# SparkFun_LoRaSerial_868MHz_-_1W.net
KiCad netlist of a schematic drawn in EAGLE
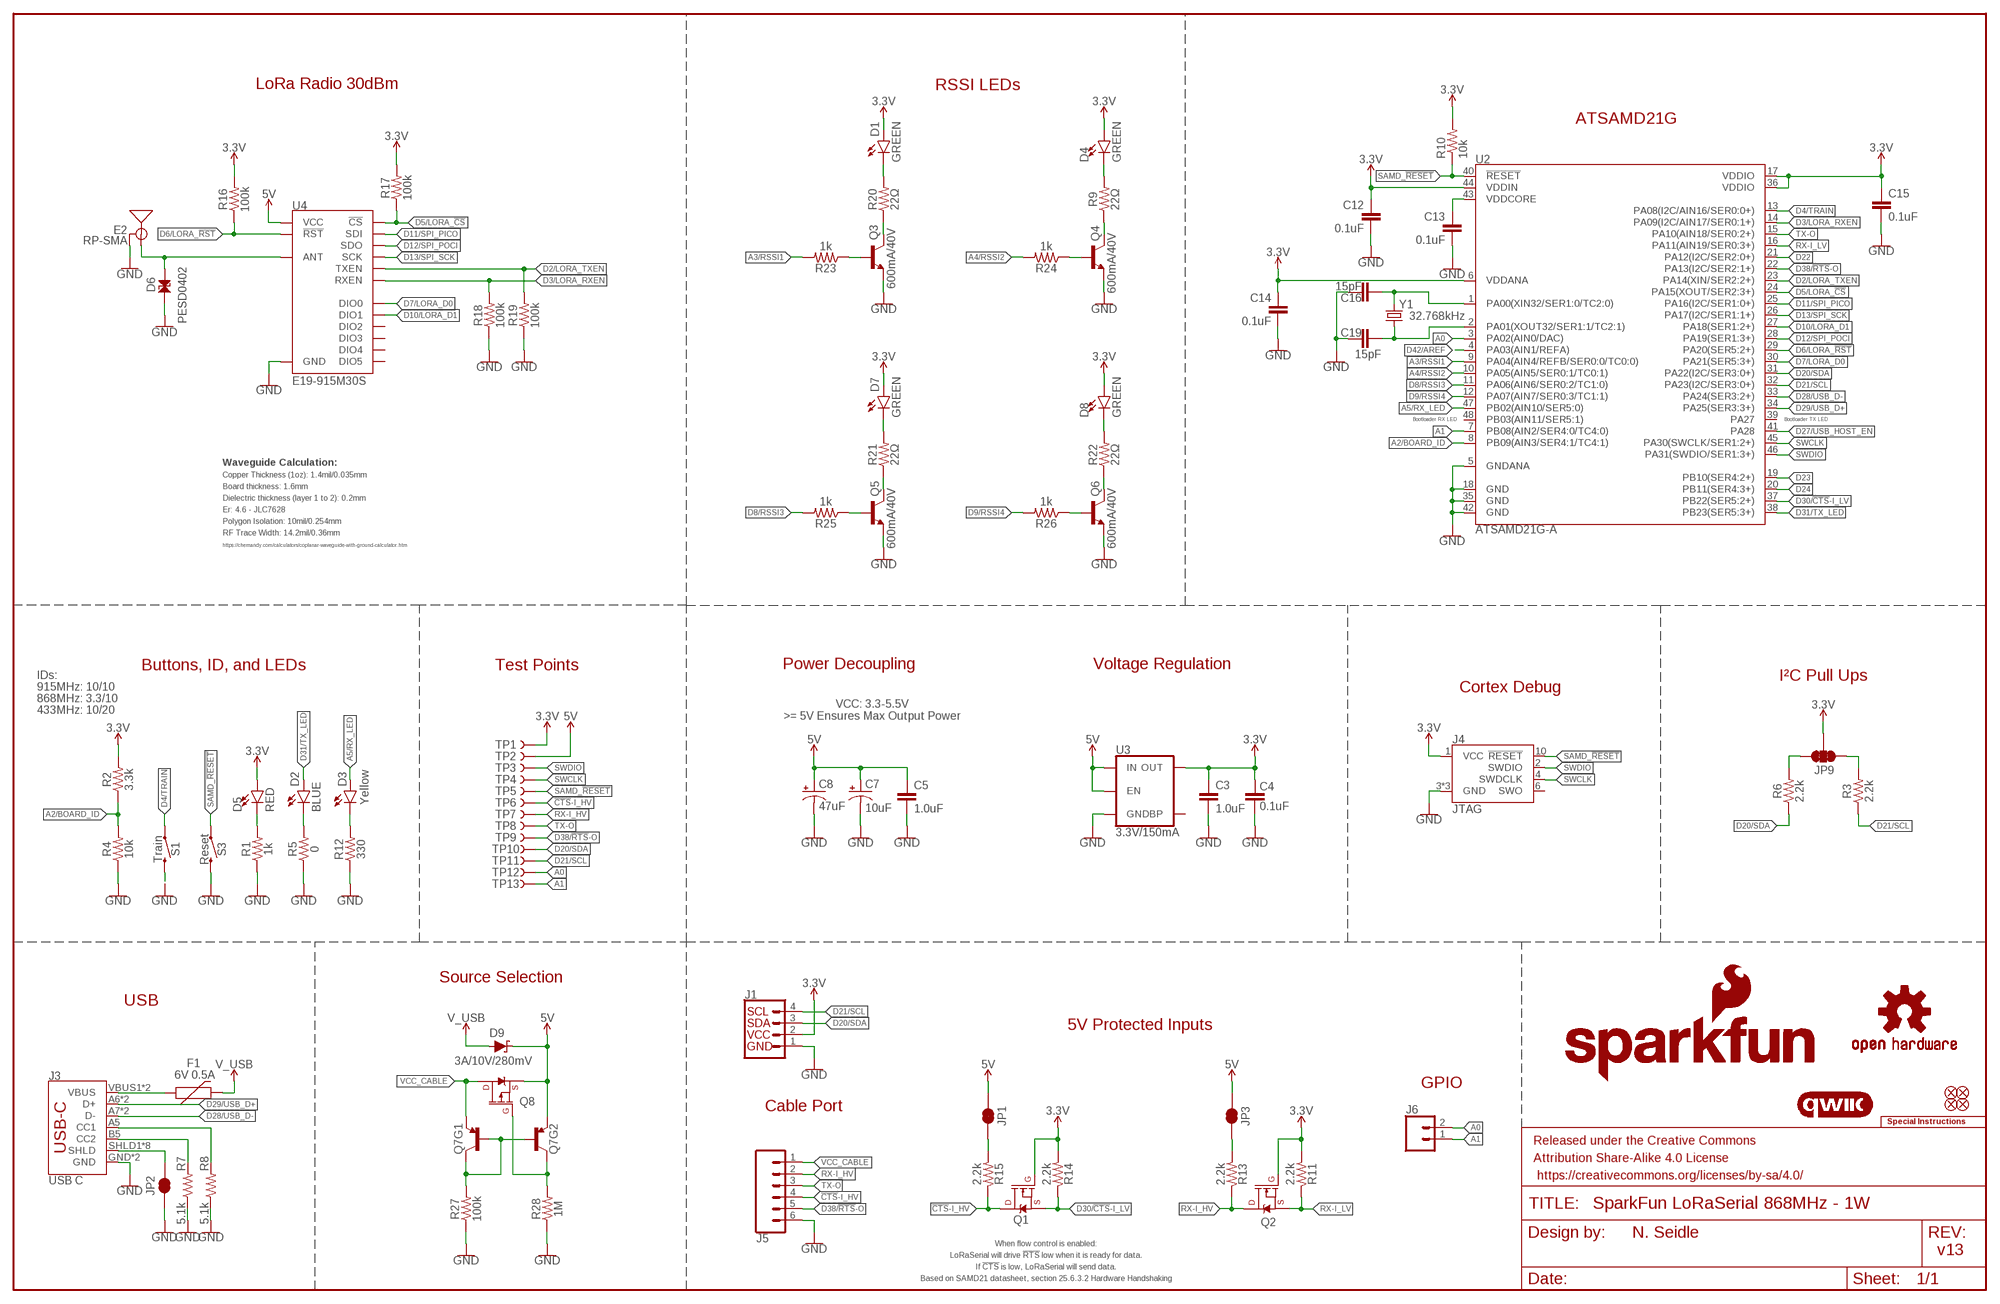
[diagram p0: schematic, sheet 1]

(export (version "E")
  (design (tool "Eeschema 10.0.6"))
  (components
    (comp (ref "C3")
      (value "1.0uF")
      (footprint "eagle-import:0603")
      (libsource (lib "eagle-import") (part "1.0UF-0603-16V-10%-X7R"))
    )
    (comp (ref "C4")
      (value "0.1uF")
      (footprint "eagle-import:0603")
      (libsource (lib "eagle-import") (part "0.1UF-0603-25V-5%"))
    )
    (comp (ref "C5")
      (value "1.0uF")
      (footprint "eagle-import:0603")
      (libsource (lib "eagle-import") (part "1.0UF-0603-16V-10%-X7R"))
    )
    (comp (ref "C7")
      (value "10uF")
      (footprint "eagle-import:EIA3216")
      (libsource (lib "eagle-import") (part "10UF-POLAR-EIA3216-16V-10%(TANT)"))
    )
    (comp (ref "C8")
      (value "47uF")
      (footprint "eagle-import:EIA3528")
      (libsource (lib "eagle-import") (part "47UF-POLAR-EIA3528-10V-10%"))
    )
    (comp (ref "C12")
      (value "0.1uF")
      (footprint "eagle-import:0603")
      (libsource (lib "eagle-import") (part "0.1UF-0603-25V-(+80/-20%)"))
    )
    (comp (ref "C13")
      (value "0.1uF")
      (footprint "eagle-import:0603")
      (libsource (lib "eagle-import") (part "0.1UF-0603-25V-(+80/-20%)"))
    )
    (comp (ref "C14")
      (value "0.1uF")
      (footprint "eagle-import:0603")
      (libsource (lib "eagle-import") (part "0.1UF-0603-25V-(+80/-20%)"))
    )
    (comp (ref "C15")
      (value "0.1uF")
      (footprint "eagle-import:0603")
      (libsource (lib "eagle-import") (part "0.1UF-0603-25V-(+80/-20%)"))
    )
    (comp (ref "C16")
      (value "15pF")
      (footprint "eagle-import:0603")
      (libsource (lib "eagle-import") (part "15PF-0603-50V-5%"))
    )
    (comp (ref "C19")
      (value "15pF")
      (footprint "eagle-import:0603")
      (libsource (lib "eagle-import") (part "15PF-0603-50V-5%"))
    )
    (comp (ref "D1")
      (value "GREEN")
      (footprint "eagle-import:LED-0603")
      (libsource (lib "eagle-import") (part "LED-GREEN0603"))
    )
    (comp (ref "D2")
      (value "BLUE")
      (footprint "eagle-import:LED-0603")
      (libsource (lib "eagle-import") (part "LED-BLUE0603"))
    )
    (comp (ref "D3")
      (value "Yellow")
      (footprint "eagle-import:LED-0603")
      (libsource (lib "eagle-import") (part "LED-YELLOW0603"))
    )
    (comp (ref "D4")
      (value "GREEN")
      (footprint "eagle-import:LED-0603")
      (libsource (lib "eagle-import") (part "LED-GREEN0603"))
    )
    (comp (ref "D5")
      (value "RED")
      (footprint "eagle-import:LED-0603")
      (libsource (lib "eagle-import") (part "LED-RED0603"))
    )
    (comp (ref "D6")
      (value "PESD0402")
      (footprint "eagle-import:0402-TIGHT")
      (libsource (lib "eagle-import") (part "PESD0402-0402T"))
    )
    (comp (ref "D7")
      (value "GREEN")
      (footprint "eagle-import:LED-0603")
      (libsource (lib "eagle-import") (part "LED-GREEN0603"))
    )
    (comp (ref "D8")
      (value "GREEN")
      (footprint "eagle-import:LED-0603")
      (libsource (lib "eagle-import") (part "LED-GREEN0603"))
    )
    (comp (ref "D9")
      (value "3A/10V/280mV")
      (footprint "eagle-import:SOD-323")
      (libsource (lib "eagle-import") (part "DIODE-SCHOTTKY-BAT60A"))
    )
    (comp (ref "E2")
      (value "RP-SMA")
      (footprint "eagle-import:SMA-EDGE")
      (libsource (lib "eagle-import") (part "ANTENNA-SMA-GROUNDEDEDGE_SMA"))
    )
    (comp (ref "F1")
      (value "6V 0.5A")
      (footprint "eagle-import:0805")
      (libsource (lib "eagle-import") (part "PPTC_6V500MA"))
    )
    (comp (ref "FID1")
      (value "FIDUCIAL1X2")
      (footprint "eagle-import:FIDUCIAL-1X2")
      (libsource (lib "eagle-import") (part "FIDUCIAL1X2"))
    )
    (comp (ref "FID2")
      (value "FIDUCIAL1X2")
      (footprint "eagle-import:FIDUCIAL-1X2")
      (libsource (lib "eagle-import") (part "FIDUCIAL1X2"))
    )
    (comp (ref "FID3")
      (value "FIDUCIAL1X2")
      (footprint "eagle-import:FIDUCIAL-1X2")
      (libsource (lib "eagle-import") (part "FIDUCIAL1X2"))
    )
    (comp (ref "FID4")
      (value "FIDUCIAL1X2")
      (footprint "eagle-import:FIDUCIAL-1X2")
      (libsource (lib "eagle-import") (part "FIDUCIAL1X2"))
    )
    (comp (ref "FRAME3")
      (value "FRAME-LEDGER")
      (footprint "eagle-import:CREATIVE_COMMONS")
      (libsource (lib "eagle-import") (part "FRAME-LEDGER"))
    )
    (comp (ref "J1")
      (value "QWIIC_RIGHT_ANGLE")
      (footprint "eagle-import:JST04_1MM_RA")
      (libsource (lib "eagle-import") (part "QWIIC_CONNECTORJS-1MM"))
    )
    (comp (ref "J3")
      (value "USB C")
      (footprint "eagle-import:USB-C-16P")
      (libsource (lib "eagle-import") (part "USB_C16PIN"))
    )
    (comp (ref "J4")
      (value "JTAG")
      (footprint "eagle-import:2X5-PTH-1.27MM-NO_SILK")
      (libsource (lib "eagle-import") (part "CORTEX_JTAG_DEBUG_MINIMUM_PTH_NS"))
    )
    (comp (ref "J5")
      (value "CONN_06JST-SMD-LOCKING")
      (footprint "eagle-import:JST-6-SMD-1.25MM-LOCKING")
      (libsource (lib "eagle-import") (part "CONN_06JST-SMD-LOCKING"))
    )
    (comp (ref "J6")
      (value "CONN_021X02_NO_SILK")
      (footprint "eagle-import:1X02_NO_SILK")
      (libsource (lib "eagle-import") (part "CONN_021X02_NO_SILK"))
    )
    (comp (ref "JP1")
      (value "JUMPER-SMT_2_NC_TRACE_SILK")
      (footprint "eagle-import:SMT-JUMPER_2_NC_TRACE_SILK")
      (libsource (lib "eagle-import") (part "JUMPER-SMT_2_NC_TRACE_SILK"))
    )
    (comp (ref "JP2")
      (value "JUMPER-SMT_2_NC_TRACE_SILK")
      (footprint "eagle-import:SMT-JUMPER_2_NC_TRACE_SILK")
      (libsource (lib "eagle-import") (part "JUMPER-SMT_2_NC_TRACE_SILK"))
    )
    (comp (ref "JP3")
      (value "JUMPER-SMT_2_NC_TRACE_SILK")
      (footprint "eagle-import:SMT-JUMPER_2_NC_TRACE_SILK")
      (libsource (lib "eagle-import") (part "JUMPER-SMT_2_NC_TRACE_SILK"))
    )
    (comp (ref "JP9")
      (value "JUMPER-SMT_3_2-NC_TRACE_SILK")
      (footprint "eagle-import:SMT-JUMPER_3_2-NC_TRACE_SILK")
      (libsource (lib "eagle-import") (part "JUMPER-SMT_3_2-NC_TRACE_SILK"))
    )
    (comp (ref "LOGO1")
      (value "SPECIAL_INSTRUCTIONS-ORDERING")
      (footprint "eagle-import:ORDERING_INSTRUCTIONS")
      (libsource (lib "eagle-import") (part "SPECIAL_INSTRUCTIONS-ORDERING"))
    )
    (comp (ref "LOGO2")
      (value "SFE_LOGO_NAME_FLAME9_MM")
      (footprint "eagle-import:SFE_LOGO_NAME_FLAME_9MM")
      (libsource (lib "eagle-import") (part "SFE_LOGO_NAME_FLAME9_MM"))
    )
    (comp (ref "LOGO3")
      (value "QWIIC_LOGO_CONNECTOR")
      (footprint "eagle-import:QWIIC_5.5MM")
      (libsource (lib "eagle-import") (part "QWIIC_LOGO_CONNECTOR"))
    )
    (comp (ref "LOGO4")
      (value "OSHW-LOGOMINI")
      (footprint "eagle-import:OSHW-LOGO-MINI")
      (libsource (lib "eagle-import") (part "OSHW-LOGOMINI"))
    )
    (comp (ref "LOGO5")
      (value "SFE_LOGO_NAME9_MM")
      (footprint "eagle-import:SFE_LOGO_NAME_9MM")
      (libsource (lib "eagle-import") (part "SFE_LOGO_NAME9_MM"))
    )
    (comp (ref "Q1")
      (value "20V/0.2A/8MHz/1.2Ω/1Vth")
      (footprint "eagle-import:SOT-416FL")
      (libsource (lib "eagle-import") (part "MOSFET-NCH-RE1C002UNTCL"))
    )
    (comp (ref "Q2")
      (value "20V/0.2A/8MHz/1.2Ω/1Vth")
      (footprint "eagle-import:SOT-416FL")
      (libsource (lib "eagle-import") (part "MOSFET-NCH-RE1C002UNTCL"))
    )
    (comp (ref "Q3")
      (value "600mA/40V")
      (footprint "eagle-import:SOT23-3")
      (libsource (lib "eagle-import") (part "TRANS_NPN-MMBT2222AL"))
    )
    (comp (ref "Q4")
      (value "600mA/40V")
      (footprint "eagle-import:SOT23-3")
      (libsource (lib "eagle-import") (part "TRANS_NPN-MMBT2222AL"))
    )
    (comp (ref "Q5")
      (value "600mA/40V")
      (footprint "eagle-import:SOT23-3")
      (libsource (lib "eagle-import") (part "TRANS_NPN-MMBT2222AL"))
    )
    (comp (ref "Q6")
      (value "600mA/40V")
      (footprint "eagle-import:SOT23-3")
      (libsource (lib "eagle-import") (part "TRANS_NPN-MMBT2222AL"))
    )
    (comp (ref "Q7")
      (value "TRANS_PNP_DUALSOT-363")
      (footprint "eagle-import:SOT363_PHILIPS")
      (libsource (lib "eagle-import") (part "TRANS_PNP_DUALSOT-363"))
    )
    (comp (ref "Q8")
      (value "20V/4.2A/52mΩ/1.4W")
      (footprint "eagle-import:SOT23-3")
      (libsource (lib "eagle-import") (part "MOSFET_PCH-DMG2305UX-7"))
    )
    (comp (ref "R1")
      (value "1k")
      (footprint "eagle-import:0603")
      (libsource (lib "eagle-import") (part "1KOHM-0603-1/10W-1%"))
    )
    (comp (ref "R2")
      (value "3.3k")
      (footprint "eagle-import:0603")
      (libsource (lib "eagle-import") (part "3.3KOHM-0603-1/10W-1%"))
    )
    (comp (ref "R3")
      (value "2.2k")
      (footprint "eagle-import:0603")
      (libsource (lib "eagle-import") (part "2.2KOHM-0603-1/10W-1%"))
    )
    (comp (ref "R4")
      (value "10k")
      (footprint "eagle-import:0603")
      (libsource (lib "eagle-import") (part "10KOHM-0603-1/10W-1%"))
    )
    (comp (ref "R5")
      (value "0")
      (footprint "eagle-import:0603")
      (libsource (lib "eagle-import") (part "0OHM-0603-1/10W"))
    )
    (comp (ref "R6")
      (value "2.2k")
      (footprint "eagle-import:0603")
      (libsource (lib "eagle-import") (part "2.2KOHM-0603-1/10W-1%"))
    )
    (comp (ref "R7")
      (value "5.1k")
      (footprint "eagle-import:0603")
      (libsource (lib "eagle-import") (part "5.1KOHM5.1KOHM-0603-1/10W-1%"))
    )
    (comp (ref "R8")
      (value "5.1k")
      (footprint "eagle-import:0603")
      (libsource (lib "eagle-import") (part "5.1KOHM5.1KOHM-0603-1/10W-1%"))
    )
    (comp (ref "R9")
      (value "22Ω")
      (footprint "eagle-import:0603")
      (libsource (lib "eagle-import") (part "22OHM-0603-1/10W-1%"))
    )
    (comp (ref "R10")
      (value "10k")
      (footprint "eagle-import:0603")
      (libsource (lib "eagle-import") (part "10KOHM-0603-1/10W-1%"))
    )
    (comp (ref "R11")
      (value "2.2k")
      (footprint "eagle-import:0603")
      (libsource (lib "eagle-import") (part "2.2KOHM-0603-1/10W-1%"))
    )
    (comp (ref "R12")
      (value "330")
      (footprint "eagle-import:0603")
      (libsource (lib "eagle-import") (part "330OHM-0603-1/10W-1%"))
    )
    (comp (ref "R13")
      (value "2.2k")
      (footprint "eagle-import:0603")
      (libsource (lib "eagle-import") (part "2.2KOHM-0603-1/10W-1%"))
    )
    (comp (ref "R14")
      (value "2.2k")
      (footprint "eagle-import:0603")
      (libsource (lib "eagle-import") (part "2.2KOHM-0603-1/10W-1%"))
    )
    (comp (ref "R15")
      (value "2.2k")
      (footprint "eagle-import:0603")
      (libsource (lib "eagle-import") (part "2.2KOHM-0603-1/10W-1%"))
    )
    (comp (ref "R16")
      (value "100k")
      (footprint "eagle-import:0603")
      (libsource (lib "eagle-import") (part "100KOHM-0603-1/10W-1%"))
    )
    (comp (ref "R17")
      (value "100k")
      (footprint "eagle-import:0603")
      (libsource (lib "eagle-import") (part "100KOHM-0603-1/10W-1%"))
    )
    (comp (ref "R18")
      (value "100k")
      (footprint "eagle-import:0603")
      (libsource (lib "eagle-import") (part "100KOHM-0603-1/10W-1%"))
    )
    (comp (ref "R19")
      (value "100k")
      (footprint "eagle-import:0603")
      (libsource (lib "eagle-import") (part "100KOHM-0603-1/10W-1%"))
    )
    (comp (ref "R20")
      (value "22Ω")
      (footprint "eagle-import:0603")
      (libsource (lib "eagle-import") (part "22OHM-0603-1/10W-1%"))
    )
    (comp (ref "R21")
      (value "22Ω")
      (footprint "eagle-import:0603")
      (libsource (lib "eagle-import") (part "22OHM-0603-1/10W-1%"))
    )
    (comp (ref "R22")
      (value "22Ω")
      (footprint "eagle-import:0603")
      (libsource (lib "eagle-import") (part "22OHM-0603-1/10W-1%"))
    )
    (comp (ref "R23")
      (value "1k")
      (footprint "eagle-import:0603")
      (libsource (lib "eagle-import") (part "1KOHM-0603-1/10W-1%"))
    )
    (comp (ref "R24")
      (value "1k")
      (footprint "eagle-import:0603")
      (libsource (lib "eagle-import") (part "1KOHM-0603-1/10W-1%"))
    )
    (comp (ref "R25")
      (value "1k")
      (footprint "eagle-import:0603")
      (libsource (lib "eagle-import") (part "1KOHM-0603-1/10W-1%"))
    )
    (comp (ref "R26")
      (value "1k")
      (footprint "eagle-import:0603")
      (libsource (lib "eagle-import") (part "1KOHM-0603-1/10W-1%"))
    )
    (comp (ref "R27")
      (value "100k")
      (footprint "eagle-import:0603")
      (libsource (lib "eagle-import") (part "100KOHM-0603-1/10W-1%"))
    )
    (comp (ref "R28")
      (value "1M")
      (footprint "eagle-import:0603")
      (libsource (lib "eagle-import") (part "1MOHM-0603-1/4W-5%"))
    )
    (comp (ref "S1")
      (value "Train")
      (footprint "eagle-import:TACTILE_SWITCH_SMD_RIGHT_ANGLE")
      (libsource (lib "eagle-import") (part "MOMENTARY-SWITCH-SPST-SMD-RIGHT-ANGLE"))
    )
    (comp (ref "S3")
      (value "Reset")
      (footprint "eagle-import:TACTILE_SWITCH_SMD_5.2MM")
      (libsource (lib "eagle-import") (part "MOMENTARY-SWITCH-SPST-SMD-5.2-TALL-REDUNDANT"))
    )
    (comp (ref "TP1")
      (value "TEST-POINT3X5")
      (footprint "eagle-import:PAD.03X.05")
      (libsource (lib "eagle-import") (part "TEST-POINT3X5"))
    )
    (comp (ref "TP2")
      (value "TEST-POINT3X5")
      (footprint "eagle-import:PAD.03X.05")
      (libsource (lib "eagle-import") (part "TEST-POINT3X5"))
    )
    (comp (ref "TP3")
      (value "TEST-POINT3X5")
      (footprint "eagle-import:PAD.03X.05")
      (libsource (lib "eagle-import") (part "TEST-POINT3X5"))
    )
    (comp (ref "TP4")
      (value "TEST-POINT3X5")
      (footprint "eagle-import:PAD.03X.05")
      (libsource (lib "eagle-import") (part "TEST-POINT3X5"))
    )
    (comp (ref "TP5")
      (value "TEST-POINT3X5")
      (footprint "eagle-import:PAD.03X.05")
      (libsource (lib "eagle-import") (part "TEST-POINT3X5"))
    )
    (comp (ref "TP6")
      (value "TEST-POINT3X5")
      (footprint "eagle-import:PAD.03X.05")
      (libsource (lib "eagle-import") (part "TEST-POINT3X5"))
    )
    (comp (ref "TP7")
      (value "TEST-POINT3X5")
      (footprint "eagle-import:PAD.03X.05")
      (libsource (lib "eagle-import") (part "TEST-POINT3X5"))
    )
    (comp (ref "TP8")
      (value "TEST-POINT3X5")
      (footprint "eagle-import:PAD.03X.05")
      (libsource (lib "eagle-import") (part "TEST-POINT3X5"))
    )
    (comp (ref "TP9")
      (value "TEST-POINT3X5")
      (footprint "eagle-import:PAD.03X.05")
      (libsource (lib "eagle-import") (part "TEST-POINT3X5"))
    )
    (comp (ref "TP10")
      (value "TEST-POINT3X5")
      (footprint "eagle-import:PAD.03X.05")
      (libsource (lib "eagle-import") (part "TEST-POINT3X5"))
    )
    (comp (ref "TP11")
      (value "TEST-POINT3X5")
      (footprint "eagle-import:PAD.03X.05")
      (libsource (lib "eagle-import") (part "TEST-POINT3X5"))
    )
    (comp (ref "TP12")
      (value "TEST-POINT3X5")
      (footprint "eagle-import:PAD.03X.05")
      (libsource (lib "eagle-import") (part "TEST-POINT3X5"))
    )
    (comp (ref "TP13")
      (value "TEST-POINT3X5")
      (footprint "eagle-import:PAD.03X.05")
      (libsource (lib "eagle-import") (part "TEST-POINT3X5"))
    )
    (comp (ref "U2")
      (value "ATSAMD21G-A")
      (footprint "eagle-import:TQFP-48")
      (libsource (lib "eagle-import") (part "ATSAMD21G-A"))
    )
    (comp (ref "U3")
      (value "3.3V/150mA")
      (footprint "eagle-import:SOT23-5")
      (libsource (lib "eagle-import") (part "V_REG_MIC52053.3V"))
    )
    (comp (ref "U4")
      (value "E19-915M30S")
      (footprint "eagle-import:E19-915M30S")
      (libsource (lib "eagle-import") (part "LORA-E19868MHZ"))
    )
    (comp (ref "Y1")
      (value "32.768kHz")
      (footprint "eagle-import:CRYSTAL-SMD-3.2X1.5MM")
      (libsource (lib "eagle-import") (part "CRYSTAL3.2X1.5MM"))
    )
  )
  (nets
    (net (code "1") (name "/D5{slash}LORA_~{CS}") (class "Default")
      (node (ref "R17") (pin "1") (pinfunction "1_1") (pintype "passive"))
      (node (ref "U2") (pin "24") (pinfunction "PA15(XOUT/SER2:3+)_24") (pintype "bidirectional"))
      (node (ref "U4") (pin "15") (pinfunction "~{CS}_15") (pintype "bidirectional"))
    )
    (net (code "2") (name "/D6{slash}LORA_~{RST}") (class "Default")
      (node (ref "R16") (pin "1") (pinfunction "1_1") (pintype "passive"))
      (node (ref "U2") (pin "29") (pinfunction "PA20(SER5:2+)_29") (pintype "bidirectional"))
      (node (ref "U4") (pin "8") (pinfunction "~{RST}_8") (pintype "bidirectional"))
    )
    (net (code "3") (name "/D30{slash}~{CTS}-I_LV") (class "Default")
      (node (ref "Q1") (pin "2") (pinfunction "S_2") (pintype "bidirectional"))
      (node (ref "R14") (pin "1") (pinfunction "1_1") (pintype "passive"))
      (node (ref "U2") (pin "37") (pinfunction "PB22(SER5:2+)_37") (pintype "bidirectional"))
    )
    (net (code "4") (name "/D38{slash}~{RTS}-O") (class "Default")
      (node (ref "J5") (pin "5") (pinfunction "5_5") (pintype "passive"))
      (node (ref "TP9") (pin "1") (pinfunction "1_1") (pintype "bidirectional"))
      (node (ref "U2") (pin "22") (pinfunction "PA13(I2C/SER2:1+)_22") (pintype "bidirectional"))
    )
    (net (code "5") (name "/SAMD_~{RESET}") (class "Default")
      (node (ref "J4") (pin "10") (pinfunction "~{RESET}_10") (pintype "bidirectional"))
      (node (ref "R10") (pin "1") (pinfunction "1_1") (pintype "passive"))
      (node (ref "S3") (pin "1") (pinfunction "1_1") (pintype "passive"))
      (node (ref "S3") (pin "2") (pinfunction "1_2") (pintype "passive"))
      (node (ref "TP5") (pin "1") (pinfunction "1_1") (pintype "bidirectional"))
      (node (ref "U2") (pin "40") (pinfunction "~{RESET}_40") (pintype "bidirectional"))
    )
    (net (code "6") (name "/~{CTS}-I_HV") (class "Default")
      (node (ref "J5") (pin "4") (pinfunction "4_4") (pintype "passive"))
      (node (ref "Q1") (pin "3") (pinfunction "D_3") (pintype "bidirectional"))
      (node (ref "R15") (pin "1") (pinfunction "1_1") (pintype "passive"))
      (node (ref "TP6") (pin "1") (pinfunction "1_1") (pintype "bidirectional"))
    )
    (net (code "7") (name "3.3V") (class "Default")
      (node (ref "C12") (pin "1") (pinfunction "1_1") (pintype "passive"))
      (node (ref "C14") (pin "1") (pinfunction "1_1") (pintype "passive"))
      (node (ref "C15") (pin "1") (pinfunction "1_1") (pintype "passive"))
      (node (ref "C3") (pin "1") (pinfunction "1_1") (pintype "passive"))
      (node (ref "C4") (pin "2") (pinfunction "2_2") (pintype "passive"))
      (node (ref "D1") (pin "A") (pinfunction "A_A") (pintype "passive"))
      (node (ref "D4") (pin "A") (pinfunction "A_A") (pintype "passive"))
      (node (ref "D5") (pin "A") (pinfunction "A_A") (pintype "passive"))
      (node (ref "D7") (pin "A") (pinfunction "A_A") (pintype "passive"))
      (node (ref "D8") (pin "A") (pinfunction "A_A") (pintype "passive"))
      (node (ref "J1") (pin "2") (pinfunction "2_2") (pintype "power_in"))
      (node (ref "J4") (pin "1") (pinfunction "VCC_1") (pintype "bidirectional"))
      (node (ref "JP9") (pin "2") (pinfunction "2_2") (pintype "passive"))
      (node (ref "Q1") (pin "1") (pinfunction "G_1") (pintype "bidirectional"))
      (node (ref "Q2") (pin "1") (pinfunction "G_1") (pintype "bidirectional"))
      (node (ref "R10") (pin "2") (pinfunction "2_2") (pintype "passive"))
      (node (ref "R11") (pin "2") (pinfunction "2_2") (pintype "passive"))
      (node (ref "R14") (pin "2") (pinfunction "2_2") (pintype "passive"))
      (node (ref "R16") (pin "2") (pinfunction "2_2") (pintype "passive"))
      (node (ref "R17") (pin "2") (pinfunction "2_2") (pintype "passive"))
      (node (ref "R2") (pin "2") (pinfunction "2_2") (pintype "passive"))
      (node (ref "TP1") (pin "1") (pinfunction "1_1") (pintype "bidirectional"))
      (node (ref "U2") (pin "17") (pinfunction "VDDIO_17") (pintype "bidirectional"))
      (node (ref "U2") (pin "36") (pinfunction "VDDIO_36") (pintype "bidirectional"))
      (node (ref "U2") (pin "44") (pinfunction "VDDIN_44") (pintype "bidirectional"))
      (node (ref "U2") (pin "6") (pinfunction "VDDANA_6") (pintype "bidirectional"))
      (node (ref "U3") (pin "5") (pinfunction "OUT_5") (pintype "passive"))
    )
    (net (code "8") (name "5V") (class "Default")
      (node (ref "C5") (pin "1") (pinfunction "1_1") (pintype "passive"))
      (node (ref "C7") (pin "+") (pinfunction "+_+") (pintype "passive"))
      (node (ref "C8") (pin "A") (pinfunction "+_A") (pintype "passive"))
      (node (ref "D9") (pin "C") (pinfunction "C_C") (pintype "passive"))
      (node (ref "JP1") (pin "2") (pinfunction "2_2") (pintype "passive"))
      (node (ref "JP3") (pin "2") (pinfunction "2_2") (pintype "passive"))
      (node (ref "Q7") (pin "4") (pinfunction "E_4") (pintype "passive"))
      (node (ref "Q8") (pin "2") (pinfunction "S_2") (pintype "bidirectional"))
      (node (ref "TP2") (pin "1") (pinfunction "1_1") (pintype "bidirectional"))
      (node (ref "U3") (pin "1") (pinfunction "IN_1") (pintype "input"))
      (node (ref "U3") (pin "3") (pinfunction "EN_3") (pintype "input"))
      (node (ref "U4") (pin "11") (pinfunction "VCC_11") (pintype "bidirectional"))
    )
    (net (code "9") (name "A0") (class "Default")
      (node (ref "J6") (pin "2") (pinfunction "2_2") (pintype "passive"))
      (node (ref "TP12") (pin "1") (pinfunction "1_1") (pintype "bidirectional"))
      (node (ref "U2") (pin "3") (pinfunction "PA02(AIN0/DAC)_3") (pintype "bidirectional"))
    )
    (net (code "10") (name "A1") (class "Default")
      (node (ref "J6") (pin "1") (pinfunction "1_1") (pintype "passive"))
      (node (ref "TP13") (pin "1") (pinfunction "1_1") (pintype "bidirectional"))
      (node (ref "U2") (pin "7") (pinfunction "PB08(AIN2/SER4:0/TC4:0)_7") (pintype "bidirectional"))
    )
    (net (code "11") (name "A2{slash}BOARD_ID") (class "Default")
      (node (ref "R2") (pin "1") (pinfunction "1_1") (pintype "passive"))
      (node (ref "R4") (pin "2") (pinfunction "2_2") (pintype "passive"))
      (node (ref "U2") (pin "8") (pinfunction "PB09(AIN3/SER4:1/TC4:1)_8") (pintype "bidirectional"))
    )
    (net (code "12") (name "A3{slash}RSSI1") (class "Default")
      (node (ref "R23") (pin "2") (pinfunction "2_2") (pintype "passive"))
      (node (ref "U2") (pin "9") (pinfunction "PA04(AIN4/REFB/SER0:0/TC0:0)_9") (pintype "bidirectional"))
    )
    (net (code "13") (name "A4{slash}RSSI2") (class "Default")
      (node (ref "R24") (pin "2") (pinfunction "2_2") (pintype "passive"))
      (node (ref "U2") (pin "10") (pinfunction "PA05(AIN5/SER0:1/TC0:1)_10") (pintype "bidirectional"))
    )
    (net (code "14") (name "A5{slash}RX_LED") (class "Default")
      (node (ref "D3") (pin "A") (pinfunction "A_A") (pintype "passive"))
      (node (ref "U2") (pin "47") (pinfunction "PB02(AIN10/SER5:0)_47") (pintype "bidirectional"))
    )
    (net (code "15") (name "D2{slash}LORA_TXEN") (class "Default")
      (node (ref "R19") (pin "2") (pinfunction "2_2") (pintype "passive"))
      (node (ref "U2") (pin "23") (pinfunction "PA14(XIN/SER2:2+)_23") (pintype "bidirectional"))
      (node (ref "U4") (pin "16") (pinfunction "TXEN_16") (pintype "bidirectional"))
    )
    (net (code "16") (name "D3{slash}LORA_RXEN") (class "Default")
      (node (ref "R18") (pin "2") (pinfunction "2_2") (pintype "passive"))
      (node (ref "U2") (pin "14") (pinfunction "PA09(I2C/AIN17/SER0:1+)_14") (pintype "bidirectional"))
      (node (ref "U4") (pin "17") (pinfunction "RXEN_17") (pintype "bidirectional"))
    )
    (net (code "17") (name "D4{slash}TRAIN") (class "Default")
      (node (ref "S1") (pin "1") (pinfunction "1_1") (pintype "passive"))
      (node (ref "U2") (pin "13") (pinfunction "PA08(I2C/AIN16/SER0:0+)_13") (pintype "bidirectional"))
    )
    (net (code "18") (name "D7{slash}LORA_D0") (class "Default")
      (node (ref "U2") (pin "30") (pinfunction "PA21(SER5:3+)_30") (pintype "bidirectional"))
      (node (ref "U4") (pin "7") (pinfunction "DIO0_7") (pintype "bidirectional"))
    )
    (net (code "19") (name "D8{slash}RSSI3") (class "Default")
      (node (ref "R25") (pin "2") (pinfunction "2_2") (pintype "passive"))
      (node (ref "U2") (pin "11") (pinfunction "PA06(AIN6/SER0:2/TC1:0)_11") (pintype "bidirectional"))
    )
    (net (code "20") (name "D9{slash}RSSI4") (class "Default")
      (node (ref "R26") (pin "2") (pinfunction "2_2") (pintype "passive"))
      (node (ref "U2") (pin "12") (pinfunction "PA07(AIN7/SER0:3/TC1:1)_12") (pintype "bidirectional"))
    )
    (net (code "21") (name "D10{slash}LORA_D1") (class "Default")
      (node (ref "U2") (pin "27") (pinfunction "PA18(SER1:2+)_27") (pintype "bidirectional"))
      (node (ref "U4") (pin "6") (pinfunction "DIO1_6") (pintype "bidirectional"))
    )
    (net (code "22") (name "D11{slash}SPI_PICO") (class "Default")
      (node (ref "U2") (pin "25") (pinfunction "PA16(I2C/SER1:0+)_25") (pintype "bidirectional"))
      (node (ref "U4") (pin "14") (pinfunction "SDI_14") (pintype "bidirectional"))
    )
    (net (code "23") (name "D12{slash}SPI_POCI") (class "Default")
      (node (ref "U2") (pin "28") (pinfunction "PA19(SER1:3+)_28") (pintype "bidirectional"))
      (node (ref "U4") (pin "13") (pinfunction "SDO_13") (pintype "bidirectional"))
    )
    (net (code "24") (name "D13{slash}SPI_SCK") (class "Default")
      (node (ref "U2") (pin "26") (pinfunction "PA17(I2C/SER1:1+)_26") (pintype "bidirectional"))
      (node (ref "U4") (pin "12") (pinfunction "SCK_12") (pintype "bidirectional"))
    )
    (net (code "25") (name "D20{slash}SDA") (class "Default")
      (node (ref "J1") (pin "3") (pinfunction "3_3") (pintype "passive"))
      (node (ref "R6") (pin "1") (pinfunction "1_1") (pintype "passive"))
      (node (ref "TP10") (pin "1") (pinfunction "1_1") (pintype "bidirectional"))
      (node (ref "U2") (pin "31") (pinfunction "PA22(I2C/SER3:0+)_31") (pintype "bidirectional"))
    )
    (net (code "26") (name "D21{slash}SCL") (class "Default")
      (node (ref "J1") (pin "4") (pinfunction "4_4") (pintype "passive"))
      (node (ref "R3") (pin "1") (pinfunction "1_1") (pintype "passive"))
      (node (ref "TP11") (pin "1") (pinfunction "1_1") (pintype "bidirectional"))
      (node (ref "U2") (pin "32") (pinfunction "PA23(I2C/SER3:0+)_32") (pintype "bidirectional"))
    )
    (net (code "27") (name "D22") (class "Default")
      (node (ref "U2") (pin "21") (pinfunction "PA12(I2C/SER2:0+)_21") (pintype "bidirectional"))
    )
    (net (code "28") (name "D23") (class "Default")
      (node (ref "U2") (pin "19") (pinfunction "PB10(SER4:2+)_19") (pintype "bidirectional"))
    )
    (net (code "29") (name "D24") (class "Default")
      (node (ref "U2") (pin "20") (pinfunction "PB11(SER4:3+)_20") (pintype "bidirectional"))
    )
    (net (code "30") (name "D27{slash}USB_HOST_EN") (class "Default")
      (node (ref "U2") (pin "41") (pinfunction "PA28_41") (pintype "bidirectional"))
    )
    (net (code "31") (name "D28{slash}USB_D-") (class "Default")
      (node (ref "J3") (pin "A7") (pinfunction "D-_A7") (pintype "bidirectional"))
      (node (ref "J3") (pin "B7") (pinfunction "D-_B7") (pintype "bidirectional"))
      (node (ref "U2") (pin "33") (pinfunction "PA24(SER3:2+)_33") (pintype "bidirectional"))
    )
    (net (code "32") (name "D29{slash}USB_D+") (class "Default")
      (node (ref "J3") (pin "A6") (pinfunction "D+_A6") (pintype "bidirectional"))
      (node (ref "J3") (pin "B6") (pinfunction "D+_B6") (pintype "bidirectional"))
      (node (ref "U2") (pin "34") (pinfunction "PA25(SER3:3+)_34") (pintype "bidirectional"))
    )
    (net (code "33") (name "D31{slash}TX_LED") (class "Default")
      (node (ref "D2") (pin "A") (pinfunction "A_A") (pintype "passive"))
      (node (ref "U2") (pin "38") (pinfunction "PB23(SER5:3+)_38") (pintype "bidirectional"))
    )
    (net (code "34") (name "D42{slash}AREF") (class "Default")
      (node (ref "U2") (pin "4") (pinfunction "PA03(AIN1/REFA)_4") (pintype "bidirectional"))
    )
    (net (code "35") (name "GND") (class "Default")
      (node (ref "C12") (pin "2") (pinfunction "2_2") (pintype "passive"))
      (node (ref "C13") (pin "2") (pinfunction "2_2") (pintype "passive"))
      (node (ref "C14") (pin "2") (pinfunction "2_2") (pintype "passive"))
      (node (ref "C15") (pin "2") (pinfunction "2_2") (pintype "passive"))
      (node (ref "C16") (pin "1") (pinfunction "1_1") (pintype "passive"))
      (node (ref "C19") (pin "2") (pinfunction "2_2") (pintype "passive"))
      (node (ref "C3") (pin "2") (pinfunction "2_2") (pintype "passive"))
      (node (ref "C4") (pin "1") (pinfunction "1_1") (pintype "passive"))
      (node (ref "C5") (pin "2") (pinfunction "2_2") (pintype "passive"))
      (node (ref "C7") (pin "-") (pinfunction "-_-") (pintype "passive"))
      (node (ref "C8") (pin "C") (pinfunction "-_C") (pintype "passive"))
      (node (ref "D6") (pin "1") (pinfunction "1_1") (pintype "bidirectional"))
      (node (ref "E2") (pin "GND@0") (pinfunction "GND_GND@0") (pintype "bidirectional"))
      (node (ref "E2") (pin "GND@1") (pinfunction "GND_GND@1") (pintype "bidirectional"))
      (node (ref "E2") (pin "GND@2") (pinfunction "GND_GND@2") (pintype "bidirectional"))
      (node (ref "E2") (pin "GND@3") (pinfunction "GND_GND@3") (pintype "bidirectional"))
      (node (ref "J1") (pin "1") (pinfunction "1_1") (pintype "power_in"))
      (node (ref "J3") (pin "GND") (pinfunction "GND_GND") (pintype "bidirectional"))
      (node (ref "J3") (pin "GND2") (pinfunction "GND_GND2") (pintype "bidirectional"))
      (node (ref "J4") (pin "3") (pinfunction "GND_3") (pintype "bidirectional"))
      (node (ref "J4") (pin "5") (pinfunction "GND_5") (pintype "bidirectional"))
      (node (ref "J4") (pin "9") (pinfunction "GND_9") (pintype "bidirectional"))
      (node (ref "J5") (pin "6") (pinfunction "6_6") (pintype "passive"))
      (node (ref "JP2") (pin "1") (pinfunction "1_1") (pintype "passive"))
      (node (ref "Q3") (pin "2") (pinfunction "E_2") (pintype "passive"))
      (node (ref "Q4") (pin "2") (pinfunction "E_2") (pintype "passive"))
      (node (ref "Q5") (pin "2") (pinfunction "E_2") (pintype "passive"))
      (node (ref "Q6") (pin "2") (pinfunction "E_2") (pintype "passive"))
      (node (ref "R1") (pin "1") (pinfunction "1_1") (pintype "passive"))
      (node (ref "R12") (pin "1") (pinfunction "1_1") (pintype "passive"))
      (node (ref "R18") (pin "1") (pinfunction "1_1") (pintype "passive"))
      (node (ref "R19") (pin "1") (pinfunction "1_1") (pintype "passive"))
      (node (ref "R27") (pin "1") (pinfunction "1_1") (pintype "passive"))
      (node (ref "R28") (pin "1") (pinfunction "1_1") (pintype "passive"))
      (node (ref "R4") (pin "1") (pinfunction "1_1") (pintype "passive"))
      (node (ref "R5") (pin "1") (pinfunction "1_1") (pintype "passive"))
      (node (ref "R7") (pin "1") (pinfunction "1_1") (pintype "passive"))
      (node (ref "R8") (pin "1") (pinfunction "1_1") (pintype "passive"))
      (node (ref "S1") (pin "2") (pinfunction "2_2") (pintype "passive"))
      (node (ref "S3") (pin "3") (pinfunction "2_3") (pintype "passive"))
      (node (ref "S3") (pin "4") (pinfunction "2_4") (pintype "passive"))
      (node (ref "U2") (pin "18") (pinfunction "GND_18") (pintype "bidirectional"))
      (node (ref "U2") (pin "35") (pinfunction "GND_35") (pintype "bidirectional"))
      (node (ref "U2") (pin "42") (pinfunction "GND_42") (pintype "bidirectional"))
      (node (ref "U2") (pin "5") (pinfunction "GNDANA_5") (pintype "bidirectional"))
      (node (ref "U3") (pin "2") (pinfunction "GND_2") (pintype "input"))
      (node (ref "U4") (pin "1") (pinfunction "GND_1") (pintype "bidirectional"))
      (node (ref "U4") (pin "10") (pinfunction "GND_10") (pintype "bidirectional"))
      (node (ref "U4") (pin "18") (pinfunction "GND_18") (pintype "bidirectional"))
      (node (ref "U4") (pin "20") (pinfunction "GND_20") (pintype "bidirectional"))
      (node (ref "U4") (pin "21") (pinfunction "GND_21") (pintype "bidirectional"))
      (node (ref "U4") (pin "22") (pinfunction "GND_22") (pintype "bidirectional"))
      (node (ref "U4") (pin "9") (pinfunction "GND_9") (pintype "bidirectional"))
    )
    (net (code "36") (name "Net-(D1-PadC)") (class "Default")
      (node (ref "D1") (pin "C") (pinfunction "C_C") (pintype "passive"))
      (node (ref "R20") (pin "2") (pinfunction "2_2") (pintype "passive"))
    )
    (net (code "37") (name "Net-(D2-PadC)") (class "Default")
      (node (ref "D2") (pin "C") (pinfunction "C_C") (pintype "passive"))
      (node (ref "R5") (pin "2") (pinfunction "2_2") (pintype "passive"))
    )
    (net (code "38") (name "Net-(D3-PadC)") (class "Default")
      (node (ref "D3") (pin "C") (pinfunction "C_C") (pintype "passive"))
      (node (ref "R12") (pin "2") (pinfunction "2_2") (pintype "passive"))
    )
    (net (code "39") (name "Net-(D4-PadC)") (class "Default")
      (node (ref "D4") (pin "C") (pinfunction "C_C") (pintype "passive"))
      (node (ref "R9") (pin "2") (pinfunction "2_2") (pintype "passive"))
    )
    (net (code "40") (name "Net-(D5-PadC)") (class "Default")
      (node (ref "D5") (pin "C") (pinfunction "C_C") (pintype "passive"))
      (node (ref "R1") (pin "2") (pinfunction "2_2") (pintype "passive"))
    )
    (net (code "41") (name "Net-(D7-PadC)") (class "Default")
      (node (ref "D7") (pin "C") (pinfunction "C_C") (pintype "passive"))
      (node (ref "R21") (pin "2") (pinfunction "2_2") (pintype "passive"))
    )
    (net (code "42") (name "Net-(D8-PadC)") (class "Default")
      (node (ref "D8") (pin "C") (pinfunction "C_C") (pintype "passive"))
      (node (ref "R22") (pin "2") (pinfunction "2_2") (pintype "passive"))
    )
    (net (code "43") (name "Net-(E2-SIGNAL)") (class "Default")
      (node (ref "D6") (pin "2") (pinfunction "2_2") (pintype "bidirectional"))
      (node (ref "E2") (pin "SIG") (pinfunction "SIGNAL_SIG") (pintype "bidirectional"))
      (node (ref "U4") (pin "19") (pinfunction "ANT_19") (pintype "bidirectional"))
    )
    (net (code "44") (name "Net-(F1-Pad1)") (class "Default")
      (node (ref "F1") (pin "1") (pinfunction "1_1") (pintype "bidirectional"))
      (node (ref "J3") (pin "VBUS1") (pinfunction "VBUS_VBUS1") (pintype "bidirectional"))
      (node (ref "J3") (pin "VBUS2") (pinfunction "VBUS_VBUS2") (pintype "bidirectional"))
    )
    (net (code "45") (name "Net-(J3-CC1)") (class "Default")
      (node (ref "J3") (pin "A5") (pinfunction "CC1_A5") (pintype "bidirectional"))
      (node (ref "R8") (pin "2") (pinfunction "2_2") (pintype "passive"))
    )
    (net (code "46") (name "Net-(J3-CC2)") (class "Default")
      (node (ref "J3") (pin "B5") (pinfunction "CC2_B5") (pintype "bidirectional"))
      (node (ref "R7") (pin "2") (pinfunction "2_2") (pintype "passive"))
    )
    (net (code "47") (name "Net-(J3-SHLD-PadSHLD1)") (class "Default")
      (node (ref "J3") (pin "SHLD1") (pinfunction "SHLD_SHLD1") (pintype "bidirectional"))
      (node (ref "J3") (pin "SHLD2") (pinfunction "SHLD_SHLD2") (pintype "bidirectional"))
      (node (ref "J3") (pin "SHLD3") (pinfunction "SHLD_SHLD3") (pintype "bidirectional"))
      (node (ref "J3") (pin "SHLD4") (pinfunction "SHLD_SHLD4") (pintype "bidirectional"))
      (node (ref "J3") (pin "SHLD5") (pinfunction "SHLD_SHLD5") (pintype "bidirectional"))
      (node (ref "J3") (pin "SHLD6") (pinfunction "SHLD_SHLD6") (pintype "bidirectional"))
      (node (ref "J3") (pin "SHLD7") (pinfunction "SHLD_SHLD7") (pintype "bidirectional"))
      (node (ref "J3") (pin "SHLD8") (pinfunction "SHLD_SHLD8") (pintype "bidirectional"))
      (node (ref "JP2") (pin "2") (pinfunction "2_2") (pintype "passive"))
    )
    (net (code "48") (name "Net-(JP1-Pad1)") (class "Default")
      (node (ref "JP1") (pin "1") (pinfunction "1_1") (pintype "passive"))
      (node (ref "R15") (pin "2") (pinfunction "2_2") (pintype "passive"))
    )
    (net (code "49") (name "Net-(JP3-Pad1)") (class "Default")
      (node (ref "JP3") (pin "1") (pinfunction "1_1") (pintype "passive"))
      (node (ref "R13") (pin "2") (pinfunction "2_2") (pintype "passive"))
    )
    (net (code "50") (name "Net-(JP9-Pad1)") (class "Default")
      (node (ref "JP9") (pin "1") (pinfunction "1_1") (pintype "passive"))
      (node (ref "R3") (pin "2") (pinfunction "2_2") (pintype "passive"))
    )
    (net (code "51") (name "Net-(JP9-Pad3)") (class "Default")
      (node (ref "JP9") (pin "3") (pinfunction "3_3") (pintype "passive"))
      (node (ref "R6") (pin "2") (pinfunction "2_2") (pintype "passive"))
    )
    (net (code "52") (name "Net-(Q3-B)") (class "Default")
      (node (ref "Q3") (pin "1") (pinfunction "B_1") (pintype "passive"))
      (node (ref "R23") (pin "1") (pinfunction "1_1") (pintype "passive"))
    )
    (net (code "53") (name "Net-(Q3-C)") (class "Default")
      (node (ref "Q3") (pin "3") (pinfunction "C_3") (pintype "passive"))
      (node (ref "R20") (pin "1") (pinfunction "1_1") (pintype "passive"))
    )
    (net (code "54") (name "Net-(Q4-B)") (class "Default")
      (node (ref "Q4") (pin "1") (pinfunction "B_1") (pintype "passive"))
      (node (ref "R24") (pin "1") (pinfunction "1_1") (pintype "passive"))
    )
    (net (code "55") (name "Net-(Q4-C)") (class "Default")
      (node (ref "Q4") (pin "3") (pinfunction "C_3") (pintype "passive"))
      (node (ref "R9") (pin "1") (pinfunction "1_1") (pintype "passive"))
    )
    (net (code "56") (name "Net-(Q5-B)") (class "Default")
      (node (ref "Q5") (pin "1") (pinfunction "B_1") (pintype "passive"))
      (node (ref "R25") (pin "1") (pinfunction "1_1") (pintype "passive"))
    )
    (net (code "57") (name "Net-(Q5-C)") (class "Default")
      (node (ref "Q5") (pin "3") (pinfunction "C_3") (pintype "passive"))
      (node (ref "R21") (pin "1") (pinfunction "1_1") (pintype "passive"))
    )
    (net (code "58") (name "Net-(Q6-B)") (class "Default")
      (node (ref "Q6") (pin "1") (pinfunction "B_1") (pintype "passive"))
      (node (ref "R26") (pin "1") (pinfunction "1_1") (pintype "passive"))
    )
    (net (code "59") (name "Net-(Q6-C)") (class "Default")
      (node (ref "Q6") (pin "3") (pinfunction "C_3") (pintype "passive"))
      (node (ref "R22") (pin "1") (pinfunction "1_1") (pintype "passive"))
    )
    (net (code "60") (name "Net-(Q7A-B)") (class "Default")
      (node (ref "Q7") (pin "2") (pinfunction "B_2") (pintype "passive"))
      (node (ref "Q7") (pin "5") (pinfunction "B_5") (pintype "passive"))
      (node (ref "Q7") (pin "6") (pinfunction "C_6") (pintype "passive"))
      (node (ref "R27") (pin "2") (pinfunction "2_2") (pintype "passive"))
    )
    (net (code "61") (name "Net-(Q7B-C)") (class "Default")
      (node (ref "Q7") (pin "3") (pinfunction "C_3") (pintype "passive"))
      (node (ref "Q8") (pin "1") (pinfunction "G_1") (pintype "bidirectional"))
      (node (ref "R28") (pin "2") (pinfunction "2_2") (pintype "passive"))
    )
    (net (code "62") (name "Net-(U2-PA00(XIN32{slash}SER1:0{slash}TC2:0))") (class "Default")
      (node (ref "C16") (pin "2") (pinfunction "2_2") (pintype "passive"))
      (node (ref "U2") (pin "1") (pinfunction "PA00(XIN32/SER1:0/TC2:0)_1") (pintype "bidirectional"))
      (node (ref "Y1") (pin "P$2") (pinfunction "2_P$2") (pintype "passive"))
    )
    (net (code "63") (name "Net-(U2-PA01(XOUT32{slash}SER1:1{slash}TC2:1))") (class "Default")
      (node (ref "C19") (pin "1") (pinfunction "1_1") (pintype "passive"))
      (node (ref "U2") (pin "2") (pinfunction "PA01(XOUT32/SER1:1/TC2:1)_2") (pintype "bidirectional"))
      (node (ref "Y1") (pin "P$1") (pinfunction "1_P$1") (pintype "passive"))
    )
    (net (code "64") (name "Net-(U2-VDDCORE)") (class "Default")
      (node (ref "C13") (pin "1") (pinfunction "1_1") (pintype "passive"))
      (node (ref "U2") (pin "43") (pinfunction "VDDCORE_43") (pintype "bidirectional"))
    )
    (net (code "65") (name "RX-I_HV") (class "Default")
      (node (ref "J5") (pin "2") (pinfunction "2_2") (pintype "passive"))
      (node (ref "Q2") (pin "3") (pinfunction "D_3") (pintype "bidirectional"))
      (node (ref "R13") (pin "1") (pinfunction "1_1") (pintype "passive"))
      (node (ref "TP7") (pin "1") (pinfunction "1_1") (pintype "bidirectional"))
    )
    (net (code "66") (name "RX-I_LV") (class "Default")
      (node (ref "Q2") (pin "2") (pinfunction "S_2") (pintype "bidirectional"))
      (node (ref "R11") (pin "1") (pinfunction "1_1") (pintype "passive"))
      (node (ref "U2") (pin "16") (pinfunction "PA11(AIN19/SER0:3+)_16") (pintype "bidirectional"))
    )
    (net (code "67") (name "SWCLK") (class "Default")
      (node (ref "J4") (pin "4") (pinfunction "SWDCLK_4") (pintype "bidirectional"))
      (node (ref "TP4") (pin "1") (pinfunction "1_1") (pintype "bidirectional"))
      (node (ref "U2") (pin "45") (pinfunction "PA30(SWCLK/SER1:2+)_45") (pintype "bidirectional"))
    )
    (net (code "68") (name "SWDIO") (class "Default")
      (node (ref "J4") (pin "2") (pinfunction "SWDIO_2") (pintype "bidirectional"))
      (node (ref "TP3") (pin "1") (pinfunction "1_1") (pintype "bidirectional"))
      (node (ref "U2") (pin "46") (pinfunction "PA31(SWDIO/SER1:3+)_46") (pintype "bidirectional"))
    )
    (net (code "69") (name "TX-O") (class "Default")
      (node (ref "J5") (pin "3") (pinfunction "3_3") (pintype "passive"))
      (node (ref "TP8") (pin "1") (pinfunction "1_1") (pintype "bidirectional"))
      (node (ref "U2") (pin "15") (pinfunction "PA10(AIN18/SER0:2+)_15") (pintype "bidirectional"))
    )
    (net (code "70") (name "VCC_CABLE") (class "Default")
      (node (ref "J5") (pin "1") (pinfunction "1_1") (pintype "passive"))
      (node (ref "Q7") (pin "1") (pinfunction "E_1") (pintype "passive"))
      (node (ref "Q8") (pin "3") (pinfunction "D_3") (pintype "bidirectional"))
    )
    (net (code "71") (name "V_USB") (class "Default")
      (node (ref "D9") (pin "A") (pinfunction "A_A") (pintype "passive"))
      (node (ref "F1") (pin "2") (pinfunction "2_2") (pintype "bidirectional"))
    )
    (net (code "72") (name "unconnected-(J4-SWO-Pad6)") (class "Default")
      (node (ref "J4") (pin "6") (pinfunction "SWO_6") (pintype "bidirectional"))
    )
    (net (code "73") (name "unconnected-(U2-PA27-Pad39)") (class "Default")
      (node (ref "U2") (pin "39") (pinfunction "PA27_39") (pintype "bidirectional"))
    )
    (net (code "74") (name "unconnected-(U2-PB03(AIN11{slash}SER5:1)-Pad48)") (class "Default")
      (node (ref "U2") (pin "48") (pinfunction "PB03(AIN11/SER5:1)_48") (pintype "bidirectional"))
    )
    (net (code "75") (name "unconnected-(U3-BP-Pad4)") (class "Default")
      (node (ref "U3") (pin "4") (pinfunction "BP_4") (pintype "input"))
    )
    (net (code "76") (name "unconnected-(U4-DIO2-Pad5)") (class "Default")
      (node (ref "U4") (pin "5") (pinfunction "DIO2_5") (pintype "bidirectional"))
    )
    (net (code "77") (name "unconnected-(U4-DIO3-Pad4)") (class "Default")
      (node (ref "U4") (pin "4") (pinfunction "DIO3_4") (pintype "bidirectional"))
    )
    (net (code "78") (name "unconnected-(U4-DIO4-Pad3)") (class "Default")
      (node (ref "U4") (pin "3") (pinfunction "DIO4_3") (pintype "bidirectional"))
    )
    (net (code "79") (name "unconnected-(U4-DIO5-Pad2)") (class "Default")
      (node (ref "U4") (pin "2") (pinfunction "DIO5_2") (pintype "bidirectional"))
    )
  )
)
